# 05_-_LCD-EEPROM-RTC.net
KiCad netlist of a schematic drawn in Altium Designer
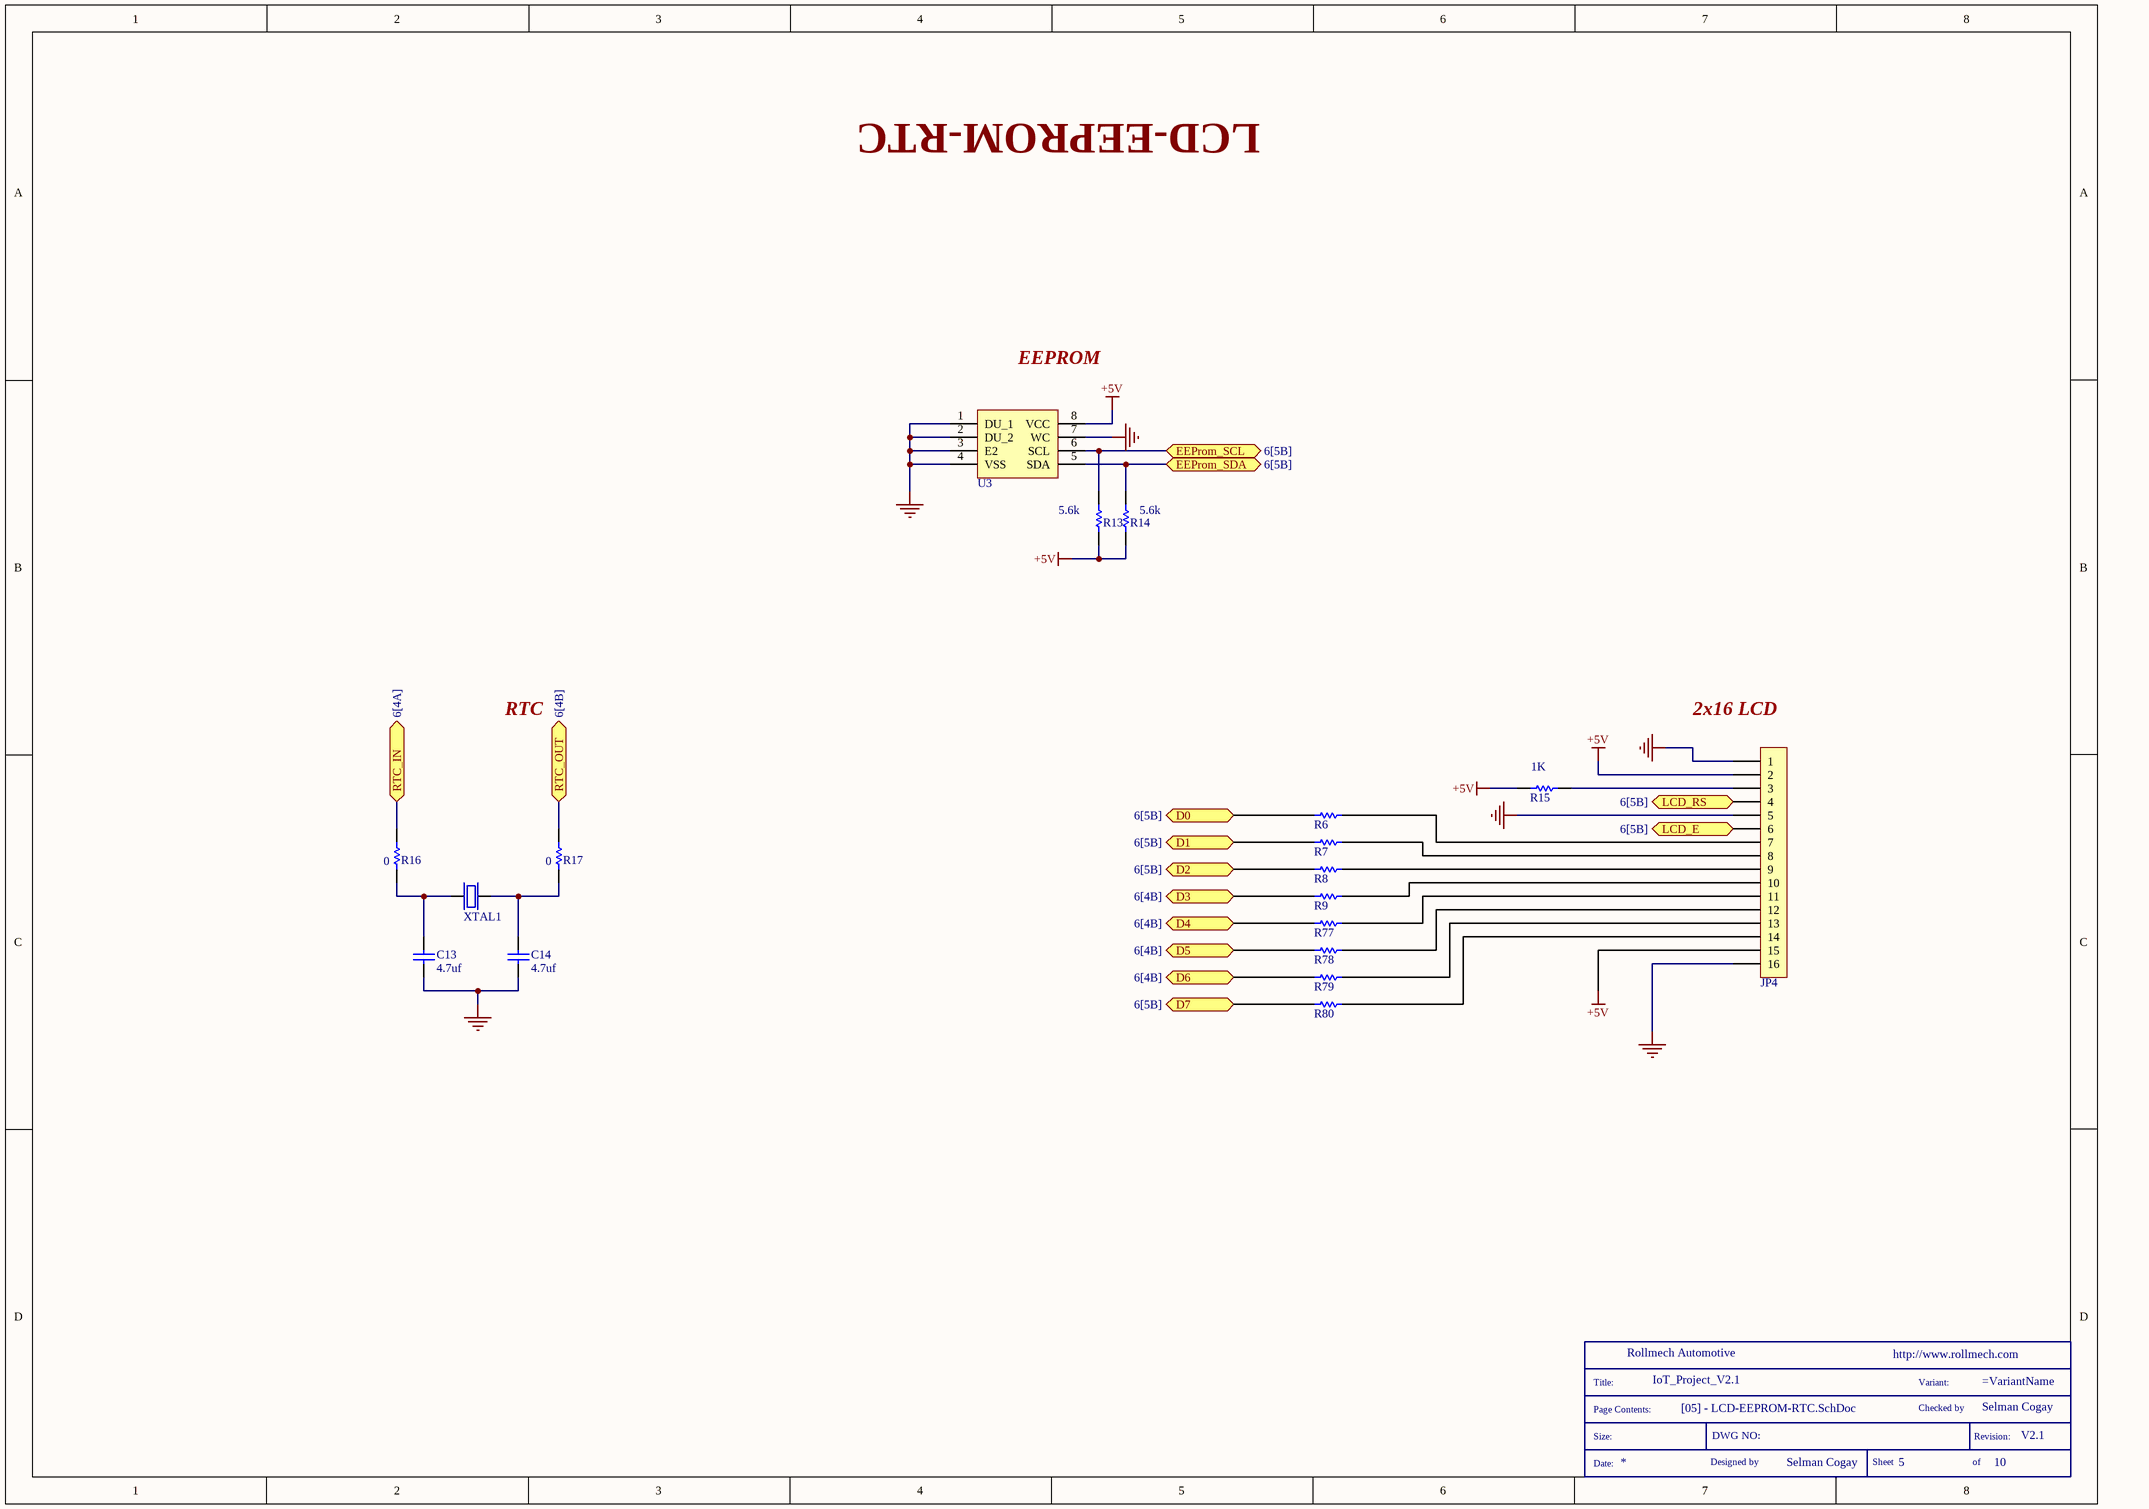
[diagram p0: [05] - LCD-EEPROM-RTC.SchDoc]

(export (version "E")
  (design (tool "Eeschema 10.0.6"))
  (components
    (comp (ref "C13")
      (value "4.7uf")
      (footprint "CAP_CER_0603")
      (description "CAP CER 4.7PF 50V C0G 0603")
      (libsource (lib "Rollmech_Altium") (part "CGA3E2C0G1H4R7C080AA"))
    )
    (comp (ref "C14")
      (value "4.7uf")
      (footprint "CAP_CER_0603")
      (description "CAP CER 4.7PF 50V C0G 0603")
      (libsource (lib "Rollmech_Altium") (part "CGA3E2C0G1H4R7C080AA"))
    )
    (comp (ref "JP4")
      (value "HDR FEMALE 1x16 2.54MM")
      (footprint "HDR_FEMALE_1x16_2.54MM")
      (libsource (lib "Rollmech_Altium") (part "PPTC161LFBN-RC"))
    )
    (comp (ref "R6")
      (value "0 1/8W")
      (footprint "RES_0805")
      (description "RES SMD 0 OHM JUMPER 1/8W 0805")
      (libsource (lib "Rollmech_Altium") (part "CRCW08050000Z0EA{dblquote}"))
    )
    (comp (ref "R7")
      (value "0 1/8W")
      (footprint "RES_0805")
      (description "RES SMD 0 OHM JUMPER 1/8W 0805")
      (libsource (lib "Rollmech_Altium") (part "CRCW08050000Z0EA{dblquote}"))
    )
    (comp (ref "R8")
      (value "0 1/8W")
      (footprint "RES_0805")
      (description "RES SMD 0 OHM JUMPER 1/8W 0805")
      (libsource (lib "Rollmech_Altium") (part "CRCW08050000Z0EA{dblquote}"))
    )
    (comp (ref "R9")
      (value "0 1/8W")
      (footprint "RES_0805")
      (description "RES SMD 0 OHM JUMPER 1/8W 0805")
      (libsource (lib "Rollmech_Altium") (part "CRCW08050000Z0EA{dblquote}"))
    )
    (comp (ref "R13")
      (value "5.6k")
      (footprint "RES_0805")
      (description "RES SMD 5.6K OHM 1% 1/8W 0805")
      (libsource (lib "Rollmech_Altium") (part "ERJ-6ENF5601V"))
    )
    (comp (ref "R14")
      (value "5.6k")
      (footprint "RES_0805")
      (description "RES SMD 5.6K OHM 1% 1/8W 0805")
      (libsource (lib "Rollmech_Altium") (part "ERJ-6ENF5601V"))
    )
    (comp (ref "R15")
      (value "1K")
      (footprint "RES_0805")
      (description "RES SMD 1K OHM")
      (libsource (lib "Rollmech_Altium") (part "ERJ-6ENF1001V"))
    )
    (comp (ref "R16")
      (value "0")
      (footprint "RES_0805")
      (description "RES SMD 0 OHM JUMPER 1/8W 0805")
      (libsource (lib "Rollmech_Altium") (part "CRCW08050000Z0EA{dblquote}"))
    )
    (comp (ref "R17")
      (value "0")
      (footprint "RES_0805")
      (description "RES SMD 0 OHM JUMPER 1/8W 0805")
      (libsource (lib "Rollmech_Altium") (part "CRCW08050000Z0EA{dblquote}"))
    )
    (comp (ref "R77")
      (value "0 1/8W")
      (footprint "RES_0805")
      (description "RES SMD 0 OHM JUMPER 1/8W 0805")
      (libsource (lib "Rollmech_Altium") (part "CRCW08050000Z0EA{dblquote}"))
    )
    (comp (ref "R78")
      (value "0 1/8W")
      (footprint "RES_0805")
      (description "RES SMD 0 OHM JUMPER 1/8W 0805")
      (libsource (lib "Rollmech_Altium") (part "CRCW08050000Z0EA{dblquote}"))
    )
    (comp (ref "R79")
      (value "0 1/8W")
      (footprint "RES_0805")
      (description "RES SMD 0 OHM JUMPER 1/8W 0805")
      (libsource (lib "Rollmech_Altium") (part "CRCW08050000Z0EA{dblquote}"))
    )
    (comp (ref "R80")
      (value "0 1/8W")
      (footprint "RES_0805")
      (description "RES SMD 0 OHM JUMPER 1/8W 0805")
      (libsource (lib "Rollmech_Altium") (part "CRCW08050000Z0EA{dblquote}"))
    )
    (comp (ref "U3")
      (value "2M EEPROM")
      (footprint "SOIC-8")
      (description "IC EEPROM 2M I2C 1MHZ 8SO")
      (libsource (lib "Rollmech_Altium") (part "M24M02-DWMN3TP/K"))
    )
    (comp (ref "XTAL1")
      (value "32.768KHZ")
      (footprint "XTAL_2SMD")
      (description "CRYSTAL 32.768KHZ")
      (libsource (lib "Rollmech_Altium") (part "ECS-.327-6-34QCS-TR"))
    )
  )
  (nets
    (net (code "1") (name "+5V") (class "Default")
      (node (ref "JP4") (pin "15") (pinfunction "15_15") (pintype "passive"))
      (node (ref "JP4") (pin "2") (pinfunction "2_2") (pintype "passive"))
      (node (ref "R13") (pin "1") (pinfunction "1_1") (pintype "passive"))
      (node (ref "R14") (pin "1") (pinfunction "1_1") (pintype "passive"))
      (node (ref "R15") (pin "1") (pinfunction "1_1") (pintype "passive"))
      (node (ref "U3") (pin "8") (pinfunction "VCC_8") (pintype "passive"))
    )
    (net (code "2") (name "/D0") (class "Default")
      (node (ref "R6") (pin "1") (pinfunction "1_1") (pintype "passive"))
    )
    (net (code "3") (name "/D1") (class "Default")
      (node (ref "R7") (pin "1") (pinfunction "1_1") (pintype "passive"))
    )
    (net (code "4") (name "/D2") (class "Default")
      (node (ref "R8") (pin "1") (pinfunction "1_1") (pintype "passive"))
    )
    (net (code "5") (name "/D3") (class "Default")
      (node (ref "R9") (pin "1") (pinfunction "1_1") (pintype "passive"))
    )
    (net (code "6") (name "/D4") (class "Default")
      (node (ref "R77") (pin "1") (pinfunction "1_1") (pintype "passive"))
    )
    (net (code "7") (name "/D5") (class "Default")
      (node (ref "R78") (pin "1") (pinfunction "1_1") (pintype "passive"))
    )
    (net (code "8") (name "/D6") (class "Default")
      (node (ref "R79") (pin "1") (pinfunction "1_1") (pintype "passive"))
    )
    (net (code "9") (name "/D7") (class "Default")
      (node (ref "R80") (pin "1") (pinfunction "1_1") (pintype "passive"))
    )
    (net (code "10") (name "/EEProm_SCL") (class "Default")
      (node (ref "R13") (pin "2") (pinfunction "2_2") (pintype "passive"))
      (node (ref "U3") (pin "6") (pinfunction "SCL_6") (pintype "passive"))
    )
    (net (code "11") (name "/EEProm_SDA") (class "Default")
      (node (ref "R14") (pin "2") (pinfunction "2_2") (pintype "passive"))
      (node (ref "U3") (pin "5") (pinfunction "SDA_5") (pintype "passive"))
    )
    (net (code "12") (name "/LCD_E") (class "Default")
      (node (ref "JP4") (pin "6") (pinfunction "6_6") (pintype "passive"))
    )
    (net (code "13") (name "/LCD_RS") (class "Default")
      (node (ref "JP4") (pin "4") (pinfunction "4_4") (pintype "passive"))
    )
    (net (code "14") (name "/RTC_IN") (class "Default")
      (node (ref "R16") (pin "2") (pinfunction "2_2") (pintype "passive"))
    )
    (net (code "15") (name "/RTC_OUT") (class "Default")
      (node (ref "R17") (pin "2") (pinfunction "2_2") (pintype "passive"))
    )
    (net (code "16") (name "GND") (class "Default")
      (node (ref "C13") (pin "1") (pinfunction "1_1") (pintype "passive"))
      (node (ref "C14") (pin "1") (pinfunction "1_1") (pintype "passive"))
      (node (ref "JP4") (pin "1") (pinfunction "1_1") (pintype "passive"))
      (node (ref "JP4") (pin "16") (pinfunction "16_16") (pintype "passive"))
      (node (ref "JP4") (pin "5") (pinfunction "5_5") (pintype "passive"))
      (node (ref "U3") (pin "1") (pinfunction "DU_1_1") (pintype "passive"))
      (node (ref "U3") (pin "2") (pinfunction "DU_2_2") (pintype "passive"))
      (node (ref "U3") (pin "3") (pinfunction "E2_3") (pintype "passive"))
      (node (ref "U3") (pin "4") (pinfunction "VSS_4") (pintype "passive"))
      (node (ref "U3") (pin "7") (pinfunction "WC_7") (pintype "passive"))
    )
    (net (code "17") (name "Net-(C13-Pad2)") (class "Default")
      (node (ref "C13") (pin "2") (pinfunction "2_2") (pintype "passive"))
      (node (ref "R16") (pin "1") (pinfunction "1_1") (pintype "passive"))
      (node (ref "XTAL1") (pin "1") (pinfunction "1_1") (pintype "passive"))
    )
    (net (code "18") (name "Net-(C14-Pad2)") (class "Default")
      (node (ref "C14") (pin "2") (pinfunction "2_2") (pintype "passive"))
      (node (ref "R17") (pin "1") (pinfunction "1_1") (pintype "passive"))
      (node (ref "XTAL1") (pin "2") (pinfunction "2_2") (pintype "passive"))
    )
    (net (code "19") (name "Net-(JP4-Pad3)") (class "Default")
      (node (ref "JP4") (pin "3") (pinfunction "3_3") (pintype "passive"))
      (node (ref "R15") (pin "2") (pinfunction "2_2") (pintype "passive"))
    )
    (net (code "20") (name "Net-(JP4-Pad7)") (class "Default")
      (node (ref "JP4") (pin "7") (pinfunction "7_7") (pintype "passive"))
      (node (ref "R6") (pin "2") (pinfunction "2_2") (pintype "passive"))
    )
    (net (code "21") (name "Net-(JP4-Pad8)") (class "Default")
      (node (ref "JP4") (pin "8") (pinfunction "8_8") (pintype "passive"))
      (node (ref "R7") (pin "2") (pinfunction "2_2") (pintype "passive"))
    )
    (net (code "22") (name "Net-(JP4-Pad9)") (class "Default")
      (node (ref "JP4") (pin "9") (pinfunction "9_9") (pintype "passive"))
      (node (ref "R8") (pin "2") (pinfunction "2_2") (pintype "passive"))
    )
    (net (code "23") (name "Net-(JP4-Pad10)") (class "Default")
      (node (ref "JP4") (pin "10") (pinfunction "10_10") (pintype "passive"))
      (node (ref "R9") (pin "2") (pinfunction "2_2") (pintype "passive"))
    )
    (net (code "24") (name "Net-(JP4-Pad11)") (class "Default")
      (node (ref "JP4") (pin "11") (pinfunction "11_11") (pintype "passive"))
      (node (ref "R77") (pin "2") (pinfunction "2_2") (pintype "passive"))
    )
    (net (code "25") (name "Net-(JP4-Pad12)") (class "Default")
      (node (ref "JP4") (pin "12") (pinfunction "12_12") (pintype "passive"))
      (node (ref "R78") (pin "2") (pinfunction "2_2") (pintype "passive"))
    )
    (net (code "26") (name "Net-(JP4-Pad13)") (class "Default")
      (node (ref "JP4") (pin "13") (pinfunction "13_13") (pintype "passive"))
      (node (ref "R79") (pin "2") (pinfunction "2_2") (pintype "passive"))
    )
    (net (code "27") (name "Net-(JP4-Pad14)") (class "Default")
      (node (ref "JP4") (pin "14") (pinfunction "14_14") (pintype "passive"))
      (node (ref "R80") (pin "2") (pinfunction "2_2") (pintype "passive"))
    )
  )
)
